# LED_rev3.net
KiCad netlist of a schematic drawn in EAGLE
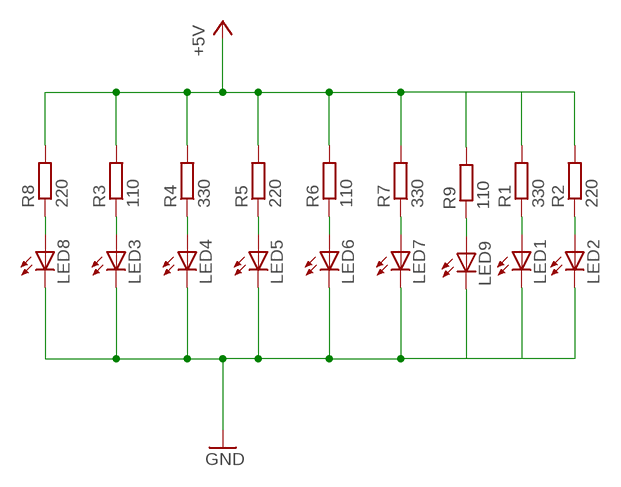
[diagram p0: schematic, sheet 1]

(export (version "E")
  (design (tool "Eeschema 10.0.6"))
  (components
    (comp (ref "LED1")
      (value "LEDCHIPLED_0603")
      (footprint "eagle-import:CHIPLED_0603")
      (libsource (lib "eagle-import") (part "LEDCHIPLED_0603"))
    )
    (comp (ref "LED2")
      (value "LEDCHIPLED_0603")
      (footprint "eagle-import:CHIPLED_0603")
      (libsource (lib "eagle-import") (part "LEDCHIPLED_0603"))
    )
    (comp (ref "LED3")
      (value "LEDCHIPLED_0603")
      (footprint "eagle-import:CHIPLED_0603")
      (libsource (lib "eagle-import") (part "LEDCHIPLED_0603"))
    )
    (comp (ref "LED4")
      (value "LEDCHIPLED_0603")
      (footprint "eagle-import:CHIPLED_0603")
      (libsource (lib "eagle-import") (part "LEDCHIPLED_0603"))
    )
    (comp (ref "LED5")
      (value "LEDCHIPLED_0603")
      (footprint "eagle-import:CHIPLED_0603")
      (libsource (lib "eagle-import") (part "LEDCHIPLED_0603"))
    )
    (comp (ref "LED6")
      (value "LEDCHIPLED_0603")
      (footprint "eagle-import:CHIPLED_0603")
      (libsource (lib "eagle-import") (part "LEDCHIPLED_0603"))
    )
    (comp (ref "LED7")
      (value "LEDCHIPLED_0603")
      (footprint "eagle-import:CHIPLED_0603")
      (libsource (lib "eagle-import") (part "LEDCHIPLED_0603"))
    )
    (comp (ref "LED8")
      (value "LEDCHIPLED_0603")
      (footprint "eagle-import:CHIPLED_0603")
      (libsource (lib "eagle-import") (part "LEDCHIPLED_0603"))
    )
    (comp (ref "LED9")
      (value "LEDCHIPLED_0603")
      (footprint "eagle-import:CHIPLED_0603")
      (libsource (lib "eagle-import") (part "LEDCHIPLED_0603"))
    )
    (comp (ref "R1")
      (value "330")
      (footprint "eagle-import:R0603")
      (libsource (lib "eagle-import") (part "R-EU_R0603"))
    )
    (comp (ref "R2")
      (value "220")
      (footprint "eagle-import:R0603")
      (libsource (lib "eagle-import") (part "R-EU_R0603"))
    )
    (comp (ref "R3")
      (value "110")
      (footprint "eagle-import:R0603")
      (libsource (lib "eagle-import") (part "R-EU_R0603"))
    )
    (comp (ref "R4")
      (value "330")
      (footprint "eagle-import:R0603")
      (libsource (lib "eagle-import") (part "R-EU_R0603"))
    )
    (comp (ref "R5")
      (value "220")
      (footprint "eagle-import:R0603")
      (libsource (lib "eagle-import") (part "R-EU_R0603"))
    )
    (comp (ref "R6")
      (value "110")
      (footprint "eagle-import:R0603")
      (libsource (lib "eagle-import") (part "R-EU_R0603"))
    )
    (comp (ref "R7")
      (value "330")
      (footprint "eagle-import:R0603")
      (libsource (lib "eagle-import") (part "R-EU_R0603"))
    )
    (comp (ref "R8")
      (value "220")
      (footprint "eagle-import:R0603")
      (libsource (lib "eagle-import") (part "R-EU_R0603"))
    )
    (comp (ref "R9")
      (value "110")
      (footprint "eagle-import:R0603")
      (libsource (lib "eagle-import") (part "R-EU_R0603"))
    )
  )
  (nets
    (net (code "1") (name "+5V") (class "Default")
      (node (ref "R1") (pin "2") (pinfunction "2_2") (pintype "passive"))
      (node (ref "R2") (pin "2") (pinfunction "2_2") (pintype "passive"))
      (node (ref "R3") (pin "2") (pinfunction "2_2") (pintype "passive"))
      (node (ref "R4") (pin "2") (pinfunction "2_2") (pintype "passive"))
      (node (ref "R5") (pin "2") (pinfunction "2_2") (pintype "passive"))
      (node (ref "R6") (pin "2") (pinfunction "2_2") (pintype "passive"))
      (node (ref "R7") (pin "2") (pinfunction "2_2") (pintype "passive"))
      (node (ref "R8") (pin "2") (pinfunction "2_2") (pintype "passive"))
      (node (ref "R9") (pin "2") (pinfunction "2_2") (pintype "passive"))
    )
    (net (code "2") (name "GND") (class "Default")
      (node (ref "LED1") (pin "C") (pinfunction "C_C") (pintype "passive"))
      (node (ref "LED2") (pin "C") (pinfunction "C_C") (pintype "passive"))
      (node (ref "LED3") (pin "C") (pinfunction "C_C") (pintype "passive"))
      (node (ref "LED4") (pin "C") (pinfunction "C_C") (pintype "passive"))
      (node (ref "LED5") (pin "C") (pinfunction "C_C") (pintype "passive"))
      (node (ref "LED6") (pin "C") (pinfunction "C_C") (pintype "passive"))
      (node (ref "LED7") (pin "C") (pinfunction "C_C") (pintype "passive"))
      (node (ref "LED8") (pin "C") (pinfunction "C_C") (pintype "passive"))
      (node (ref "LED9") (pin "C") (pinfunction "C_C") (pintype "passive"))
    )
    (net (code "3") (name "Net-(LED1-PadA)") (class "Default")
      (node (ref "LED1") (pin "A") (pinfunction "A_A") (pintype "passive"))
      (node (ref "R1") (pin "1") (pinfunction "1_1") (pintype "passive"))
    )
    (net (code "4") (name "Net-(LED2-PadA)") (class "Default")
      (node (ref "LED2") (pin "A") (pinfunction "A_A") (pintype "passive"))
      (node (ref "R2") (pin "1") (pinfunction "1_1") (pintype "passive"))
    )
    (net (code "5") (name "Net-(LED3-PadA)") (class "Default")
      (node (ref "LED3") (pin "A") (pinfunction "A_A") (pintype "passive"))
      (node (ref "R3") (pin "1") (pinfunction "1_1") (pintype "passive"))
    )
    (net (code "6") (name "Net-(LED4-PadA)") (class "Default")
      (node (ref "LED4") (pin "A") (pinfunction "A_A") (pintype "passive"))
      (node (ref "R4") (pin "1") (pinfunction "1_1") (pintype "passive"))
    )
    (net (code "7") (name "Net-(LED5-PadA)") (class "Default")
      (node (ref "LED5") (pin "A") (pinfunction "A_A") (pintype "passive"))
      (node (ref "R5") (pin "1") (pinfunction "1_1") (pintype "passive"))
    )
    (net (code "8") (name "Net-(LED6-PadA)") (class "Default")
      (node (ref "LED6") (pin "A") (pinfunction "A_A") (pintype "passive"))
      (node (ref "R6") (pin "1") (pinfunction "1_1") (pintype "passive"))
    )
    (net (code "9") (name "Net-(LED7-PadA)") (class "Default")
      (node (ref "LED7") (pin "A") (pinfunction "A_A") (pintype "passive"))
      (node (ref "R7") (pin "1") (pinfunction "1_1") (pintype "passive"))
    )
    (net (code "10") (name "Net-(LED8-PadA)") (class "Default")
      (node (ref "LED8") (pin "A") (pinfunction "A_A") (pintype "passive"))
      (node (ref "R8") (pin "1") (pinfunction "1_1") (pintype "passive"))
    )
    (net (code "11") (name "Net-(LED9-PadA)") (class "Default")
      (node (ref "LED9") (pin "A") (pinfunction "A_A") (pintype "passive"))
      (node (ref "R9") (pin "1") (pinfunction "1_1") (pintype "passive"))
    )
  )
)
